# Driver.net
KiCad netlist of a schematic drawn in EAGLE
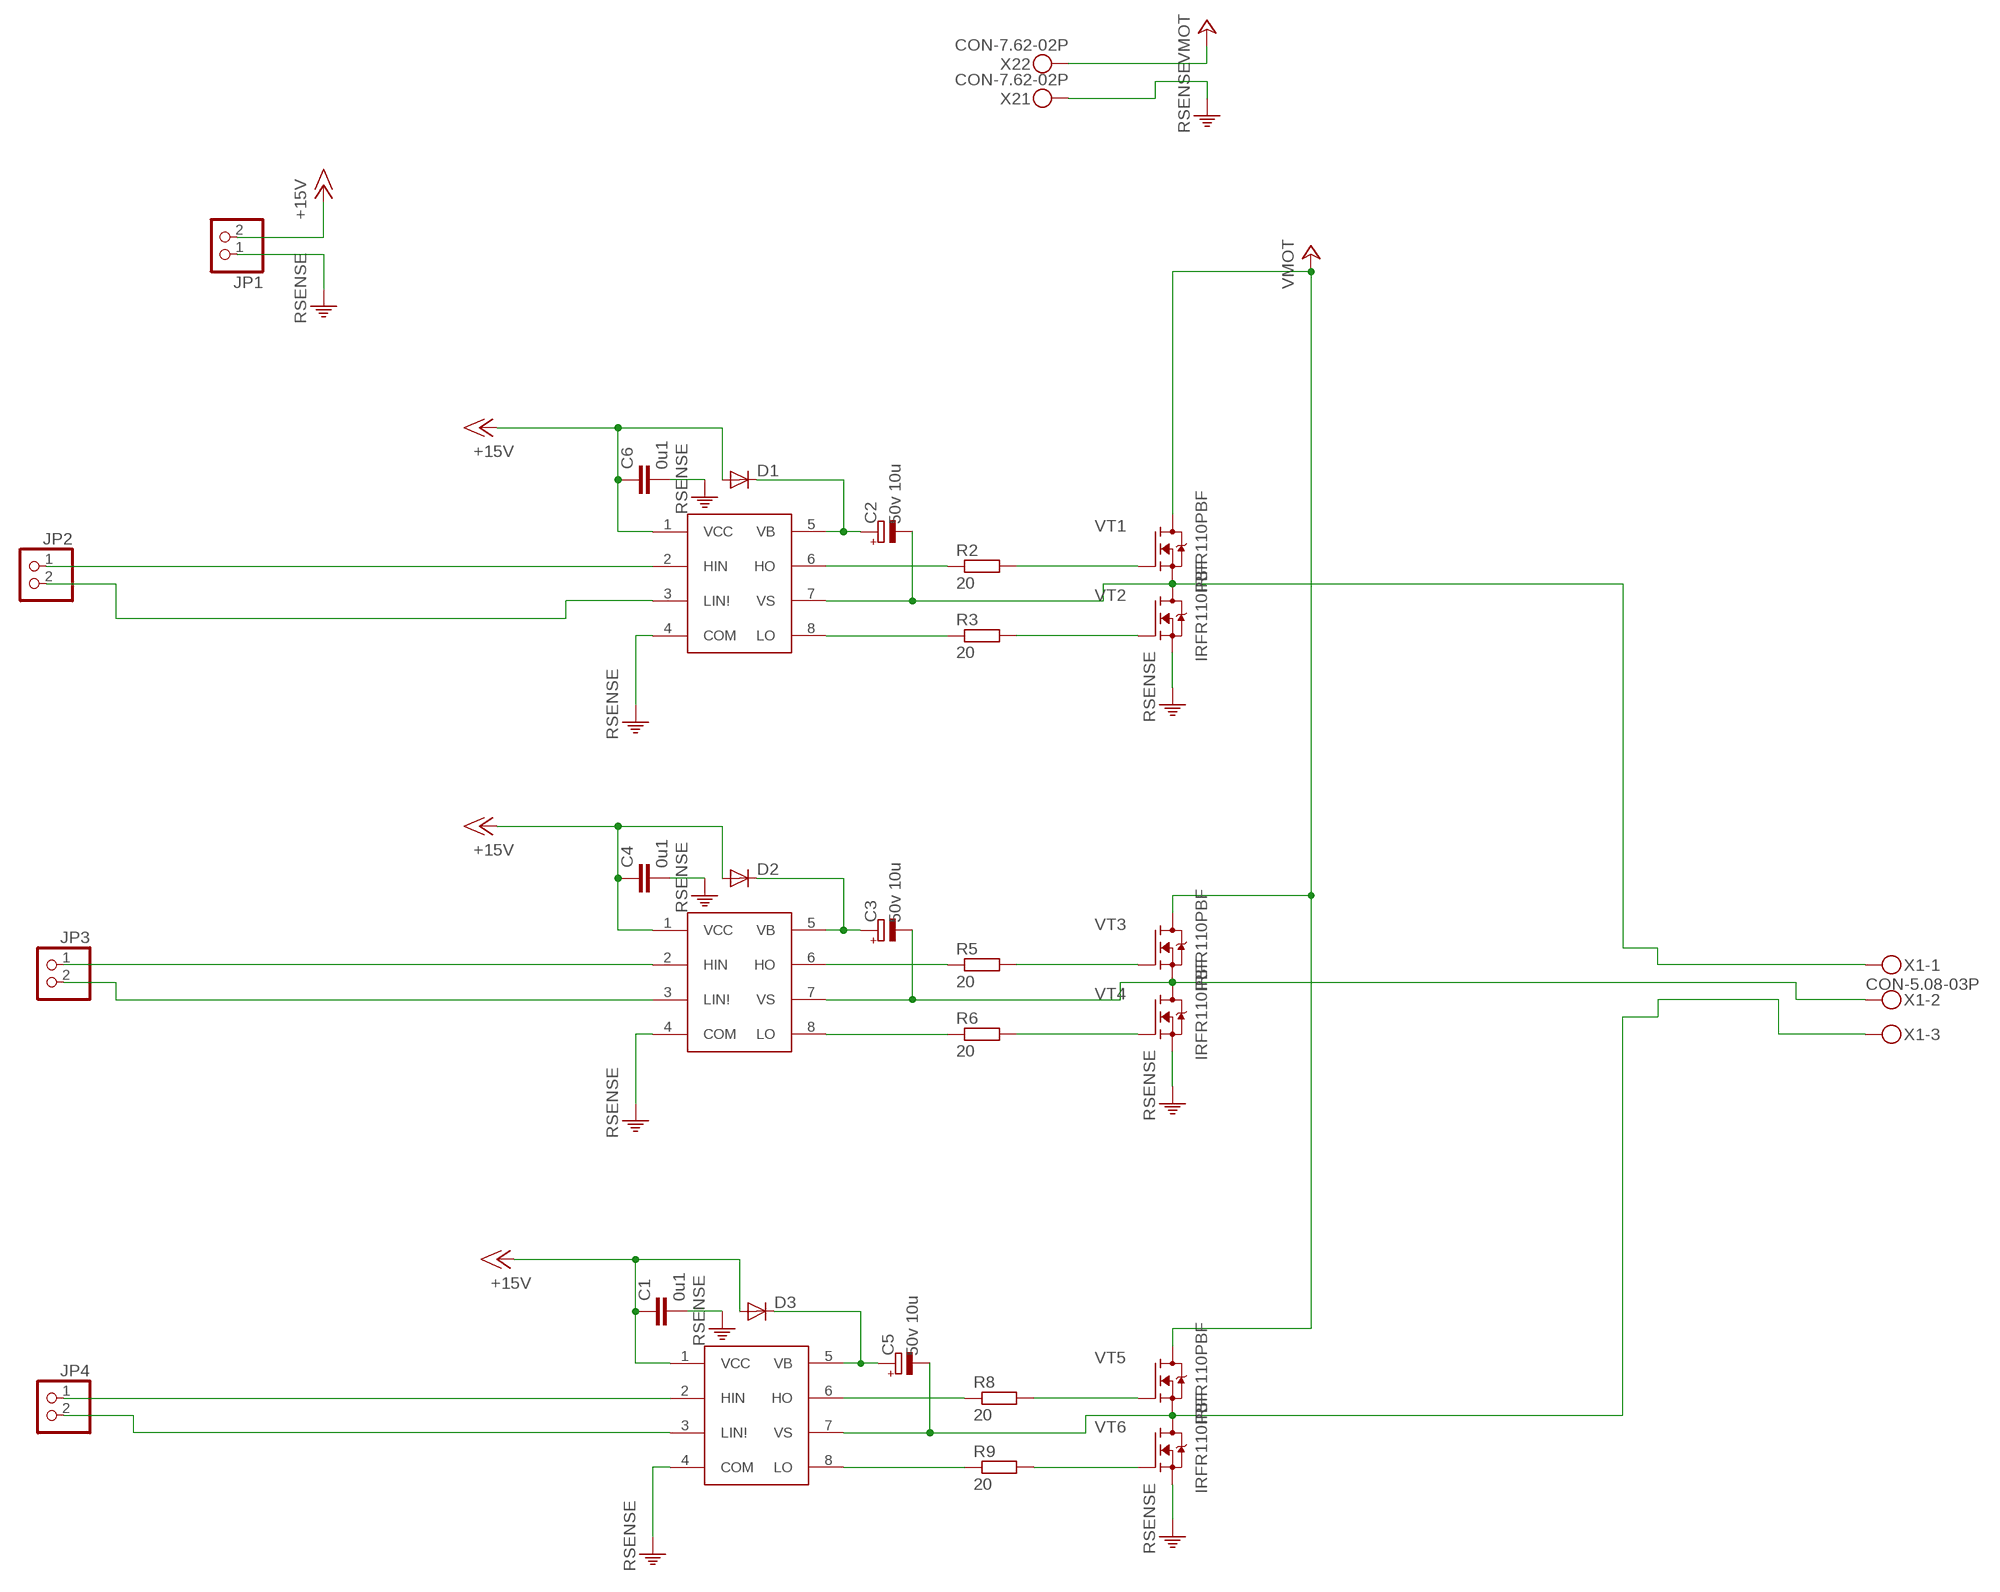
[diagram p0: schematic, sheet 1]

(export (version "E")
  (design (tool "Eeschema 10.0.6"))
  (components
    (comp (ref "C1")
      (value "0u1")
      (footprint "eagle-import:C0805")
      (libsource (lib "eagle-import") (part "CAP_0805"))
    )
    (comp (ref "C2")
      (value "50v 10u")
      (footprint "eagle-import:E2,5-7")
      (libsource (lib "eagle-import") (part "CAP-POL_E2.5-7"))
    )
    (comp (ref "C3")
      (value "50v 10u")
      (footprint "eagle-import:E2,5-7")
      (libsource (lib "eagle-import") (part "CAP-POL_E2.5-7"))
    )
    (comp (ref "C4")
      (value "0u1")
      (footprint "eagle-import:C0805")
      (libsource (lib "eagle-import") (part "CAP_0805"))
    )
    (comp (ref "C5")
      (value "50v 10u")
      (footprint "eagle-import:E2,5-7")
      (libsource (lib "eagle-import") (part "CAP-POL_E2.5-7"))
    )
    (comp (ref "C6")
      (value "0u1")
      (footprint "eagle-import:C0805")
      (libsource (lib "eagle-import") (part "CAP_0805"))
    )
    (comp (ref "D1")
      (value "DIODE_ES1J")
      (footprint "eagle-import:DO214AC")
      (libsource (lib "eagle-import") (part "DIODE_ES1J"))
    )
    (comp (ref "D2")
      (value "DIODE_ES1J")
      (footprint "eagle-import:DO214AC")
      (libsource (lib "eagle-import") (part "DIODE_ES1J"))
    )
    (comp (ref "D3")
      (value "DIODE_ES1J")
      (footprint "eagle-import:DO214AC")
      (libsource (lib "eagle-import") (part "DIODE_ES1J"))
    )
    (comp (ref "IC-1")
      (value "IC-IR2103")
      (footprint "eagle-import:SO8")
      (libsource (lib "eagle-import") (part "IC-IR2103"))
    )
    (comp (ref "IC-2")
      (value "IC-IR2103")
      (footprint "eagle-import:SO8")
      (libsource (lib "eagle-import") (part "IC-IR2103"))
    )
    (comp (ref "IC-3")
      (value "IC-IR2103")
      (footprint "eagle-import:SO8")
      (libsource (lib "eagle-import") (part "IC-IR2103"))
    )
    (comp (ref "JP1")
      (value "PINHD-1X2")
      (footprint "eagle-import:1X02")
      (libsource (lib "eagle-import") (part "PINHD-1X2"))
    )
    (comp (ref "JP2")
      (value "PINHD-1X2")
      (footprint "eagle-import:1X02")
      (libsource (lib "eagle-import") (part "PINHD-1X2"))
    )
    (comp (ref "JP3")
      (value "PINHD-1X2")
      (footprint "eagle-import:1X02")
      (libsource (lib "eagle-import") (part "PINHD-1X2"))
    )
    (comp (ref "JP4")
      (value "PINHD-1X2")
      (footprint "eagle-import:1X02")
      (libsource (lib "eagle-import") (part "PINHD-1X2"))
    )
    (comp (ref "R2")
      (value "20")
      (footprint "eagle-import:R0805")
      (libsource (lib "eagle-import") (part "R_0805"))
    )
    (comp (ref "R3")
      (value "20")
      (footprint "eagle-import:R0805")
      (libsource (lib "eagle-import") (part "R_0805"))
    )
    (comp (ref "R5")
      (value "20")
      (footprint "eagle-import:R0805")
      (libsource (lib "eagle-import") (part "R_0805"))
    )
    (comp (ref "R6")
      (value "20")
      (footprint "eagle-import:R0805")
      (libsource (lib "eagle-import") (part "R_0805"))
    )
    (comp (ref "R8")
      (value "20")
      (footprint "eagle-import:R0805")
      (libsource (lib "eagle-import") (part "R_0805"))
    )
    (comp (ref "R9")
      (value "20")
      (footprint "eagle-import:R0805")
      (libsource (lib "eagle-import") (part "R_0805"))
    )
    (comp (ref "VT1")
      (value "IRFR110PBF")
      (footprint "eagle-import:DPAK")
      (libsource (lib "eagle-import") (part "FET-NDPAK"))
    )
    (comp (ref "VT2")
      (value "IRFR110PBF")
      (footprint "eagle-import:DPAK")
      (libsource (lib "eagle-import") (part "FET-NDPAK"))
    )
    (comp (ref "VT3")
      (value "IRFR110PBF")
      (footprint "eagle-import:DPAK")
      (libsource (lib "eagle-import") (part "FET-NDPAK"))
    )
    (comp (ref "VT4")
      (value "IRFR110PBF")
      (footprint "eagle-import:DPAK")
      (libsource (lib "eagle-import") (part "FET-NDPAK"))
    )
    (comp (ref "VT5")
      (value "IRFR110PBF")
      (footprint "eagle-import:DPAK")
      (libsource (lib "eagle-import") (part "FET-NDPAK"))
    )
    (comp (ref "VT6")
      (value "IRFR110PBF")
      (footprint "eagle-import:DPAK")
      (libsource (lib "eagle-import") (part "FET-NDPAK"))
    )
    (comp (ref "X1")
      (value "CON-5.08-03P")
      (footprint "eagle-import:MKDSN1,5_3-5,08")
      (libsource (lib "eagle-import") (part "CON-5.08-03P"))
    )
    (comp (ref "X2")
      (value "CON-7.62-02P")
      (footprint "eagle-import:KF25C-7.62-02P-13")
      (libsource (lib "eagle-import") (part "CON-7.62-02P"))
    )
  )
  (nets
    (net (code "1") (name "+15V") (class "Default")
      (node (ref "C1") (pin "1") (pinfunction "1_1") (pintype "passive"))
      (node (ref "C4") (pin "1") (pinfunction "1_1") (pintype "passive"))
      (node (ref "C6") (pin "1") (pinfunction "1_1") (pintype "passive"))
      (node (ref "D1") (pin "A") (pinfunction "A_A") (pintype "passive"))
      (node (ref "D2") (pin "A") (pinfunction "A_A") (pintype "passive"))
      (node (ref "D3") (pin "A") (pinfunction "A_A") (pintype "passive"))
      (node (ref "IC-1") (pin "1") (pinfunction "VCC_1") (pintype "bidirectional"))
      (node (ref "IC-2") (pin "1") (pinfunction "VCC_1") (pintype "bidirectional"))
      (node (ref "IC-3") (pin "1") (pinfunction "VCC_1") (pintype "bidirectional"))
      (node (ref "JP1") (pin "2") (pinfunction "2_2") (pintype "passive"))
    )
    (net (code "2") (name "Net-(IC-1-HIN)") (class "Default")
      (node (ref "IC-1") (pin "2") (pinfunction "HIN_2") (pintype "bidirectional"))
      (node (ref "JP2") (pin "1") (pinfunction "1_1") (pintype "passive"))
    )
    (net (code "3") (name "Net-(IC-1-HO)") (class "Default")
      (node (ref "IC-1") (pin "6") (pinfunction "HO_6") (pintype "bidirectional"))
      (node (ref "R2") (pin "1") (pinfunction "1_1") (pintype "passive"))
    )
    (net (code "4") (name "Net-(IC-1-LIN~{})") (class "Default")
      (node (ref "IC-1") (pin "3") (pinfunction "LIN~{}_3") (pintype "bidirectional"))
      (node (ref "JP2") (pin "2") (pinfunction "2_2") (pintype "passive"))
    )
    (net (code "5") (name "Net-(IC-1-LO)") (class "Default")
      (node (ref "IC-1") (pin "8") (pinfunction "LO_8") (pintype "bidirectional"))
      (node (ref "R3") (pin "1") (pinfunction "1_1") (pintype "passive"))
    )
    (net (code "6") (name "Net-(IC-1-VB)") (class "Default")
      (node (ref "C2") (pin "+") (pinfunction "+_+") (pintype "passive"))
      (node (ref "D1") (pin "C") (pinfunction "C_C") (pintype "passive"))
      (node (ref "IC-1") (pin "5") (pinfunction "VB_5") (pintype "bidirectional"))
    )
    (net (code "7") (name "Net-(IC-1-VS)") (class "Default")
      (node (ref "C2") (pin "-") (pinfunction "-_-") (pintype "passive"))
      (node (ref "IC-1") (pin "7") (pinfunction "VS_7") (pintype "bidirectional"))
      (node (ref "VT1") (pin "S") (pinfunction "S_S") (pintype "passive"))
      (node (ref "VT2") (pin "D") (pinfunction "D_D") (pintype "passive"))
      (node (ref "X1") (pin "1") (pinfunction "KL_1") (pintype "passive"))
    )
    (net (code "8") (name "Net-(IC-2-HIN)") (class "Default")
      (node (ref "IC-2") (pin "2") (pinfunction "HIN_2") (pintype "bidirectional"))
      (node (ref "JP3") (pin "1") (pinfunction "1_1") (pintype "passive"))
    )
    (net (code "9") (name "Net-(IC-2-HO)") (class "Default")
      (node (ref "IC-2") (pin "6") (pinfunction "HO_6") (pintype "bidirectional"))
      (node (ref "R5") (pin "1") (pinfunction "1_1") (pintype "passive"))
    )
    (net (code "10") (name "Net-(IC-2-LIN~{})") (class "Default")
      (node (ref "IC-2") (pin "3") (pinfunction "LIN~{}_3") (pintype "bidirectional"))
      (node (ref "JP3") (pin "2") (pinfunction "2_2") (pintype "passive"))
    )
    (net (code "11") (name "Net-(IC-2-LO)") (class "Default")
      (node (ref "IC-2") (pin "8") (pinfunction "LO_8") (pintype "bidirectional"))
      (node (ref "R6") (pin "1") (pinfunction "1_1") (pintype "passive"))
    )
    (net (code "12") (name "Net-(IC-2-VB)") (class "Default")
      (node (ref "C3") (pin "+") (pinfunction "+_+") (pintype "passive"))
      (node (ref "D2") (pin "C") (pinfunction "C_C") (pintype "passive"))
      (node (ref "IC-2") (pin "5") (pinfunction "VB_5") (pintype "bidirectional"))
    )
    (net (code "13") (name "Net-(IC-2-VS)") (class "Default")
      (node (ref "C3") (pin "-") (pinfunction "-_-") (pintype "passive"))
      (node (ref "IC-2") (pin "7") (pinfunction "VS_7") (pintype "bidirectional"))
      (node (ref "VT3") (pin "S") (pinfunction "S_S") (pintype "passive"))
      (node (ref "VT4") (pin "D") (pinfunction "D_D") (pintype "passive"))
      (node (ref "X1") (pin "2") (pinfunction "KL_2") (pintype "passive"))
    )
    (net (code "14") (name "Net-(IC-3-HIN)") (class "Default")
      (node (ref "IC-3") (pin "2") (pinfunction "HIN_2") (pintype "bidirectional"))
      (node (ref "JP4") (pin "1") (pinfunction "1_1") (pintype "passive"))
    )
    (net (code "15") (name "Net-(IC-3-HO)") (class "Default")
      (node (ref "IC-3") (pin "6") (pinfunction "HO_6") (pintype "bidirectional"))
      (node (ref "R8") (pin "1") (pinfunction "1_1") (pintype "passive"))
    )
    (net (code "16") (name "Net-(IC-3-LIN~{})") (class "Default")
      (node (ref "IC-3") (pin "3") (pinfunction "LIN~{}_3") (pintype "bidirectional"))
      (node (ref "JP4") (pin "2") (pinfunction "2_2") (pintype "passive"))
    )
    (net (code "17") (name "Net-(IC-3-LO)") (class "Default")
      (node (ref "IC-3") (pin "8") (pinfunction "LO_8") (pintype "bidirectional"))
      (node (ref "R9") (pin "1") (pinfunction "1_1") (pintype "passive"))
    )
    (net (code "18") (name "Net-(IC-3-VB)") (class "Default")
      (node (ref "C5") (pin "+") (pinfunction "+_+") (pintype "passive"))
      (node (ref "D3") (pin "C") (pinfunction "C_C") (pintype "passive"))
      (node (ref "IC-3") (pin "5") (pinfunction "VB_5") (pintype "bidirectional"))
    )
    (net (code "19") (name "Net-(IC-3-VS)") (class "Default")
      (node (ref "C5") (pin "-") (pinfunction "-_-") (pintype "passive"))
      (node (ref "IC-3") (pin "7") (pinfunction "VS_7") (pintype "bidirectional"))
      (node (ref "VT5") (pin "S") (pinfunction "S_S") (pintype "passive"))
      (node (ref "VT6") (pin "D") (pinfunction "D_D") (pintype "passive"))
      (node (ref "X1") (pin "3") (pinfunction "KL_3") (pintype "passive"))
    )
    (net (code "20") (name "Net-(R2-Pad2)") (class "Default")
      (node (ref "R2") (pin "2") (pinfunction "2_2") (pintype "passive"))
      (node (ref "VT1") (pin "G") (pinfunction "G_G") (pintype "passive"))
    )
    (net (code "21") (name "Net-(R3-Pad2)") (class "Default")
      (node (ref "R3") (pin "2") (pinfunction "2_2") (pintype "passive"))
      (node (ref "VT2") (pin "G") (pinfunction "G_G") (pintype "passive"))
    )
    (net (code "22") (name "Net-(R5-Pad2)") (class "Default")
      (node (ref "R5") (pin "2") (pinfunction "2_2") (pintype "passive"))
      (node (ref "VT3") (pin "G") (pinfunction "G_G") (pintype "passive"))
    )
    (net (code "23") (name "Net-(R6-Pad2)") (class "Default")
      (node (ref "R6") (pin "2") (pinfunction "2_2") (pintype "passive"))
      (node (ref "VT4") (pin "G") (pinfunction "G_G") (pintype "passive"))
    )
    (net (code "24") (name "Net-(R8-Pad2)") (class "Default")
      (node (ref "R8") (pin "2") (pinfunction "2_2") (pintype "passive"))
      (node (ref "VT5") (pin "G") (pinfunction "G_G") (pintype "passive"))
    )
    (net (code "25") (name "Net-(R9-Pad2)") (class "Default")
      (node (ref "R9") (pin "2") (pinfunction "2_2") (pintype "passive"))
      (node (ref "VT6") (pin "G") (pinfunction "G_G") (pintype "passive"))
    )
    (net (code "26") (name "RSENSE") (class "Default")
      (node (ref "C1") (pin "2") (pinfunction "2_2") (pintype "passive"))
      (node (ref "C4") (pin "2") (pinfunction "2_2") (pintype "passive"))
      (node (ref "C6") (pin "2") (pinfunction "2_2") (pintype "passive"))
      (node (ref "IC-1") (pin "4") (pinfunction "COM_4") (pintype "bidirectional"))
      (node (ref "IC-2") (pin "4") (pinfunction "COM_4") (pintype "bidirectional"))
      (node (ref "IC-3") (pin "4") (pinfunction "COM_4") (pintype "bidirectional"))
      (node (ref "JP1") (pin "1") (pinfunction "1_1") (pintype "passive"))
      (node (ref "VT2") (pin "S") (pinfunction "S_S") (pintype "passive"))
      (node (ref "VT4") (pin "S") (pinfunction "S_S") (pintype "passive"))
      (node (ref "VT6") (pin "S") (pinfunction "S_S") (pintype "passive"))
      (node (ref "X2") (pin "P$1") (pinfunction "KL_P$1") (pintype "passive"))
    )
    (net (code "27") (name "VMOT") (class "Default")
      (node (ref "VT1") (pin "D") (pinfunction "D_D") (pintype "passive"))
      (node (ref "VT3") (pin "D") (pinfunction "D_D") (pintype "passive"))
      (node (ref "VT5") (pin "D") (pinfunction "D_D") (pintype "passive"))
      (node (ref "X2") (pin "P$2") (pinfunction "KL_P$2") (pintype "passive"))
    )
  )
)
